# Water-Volume-Monitoring.net
KiCad netlist of a schematic drawn in EAGLE
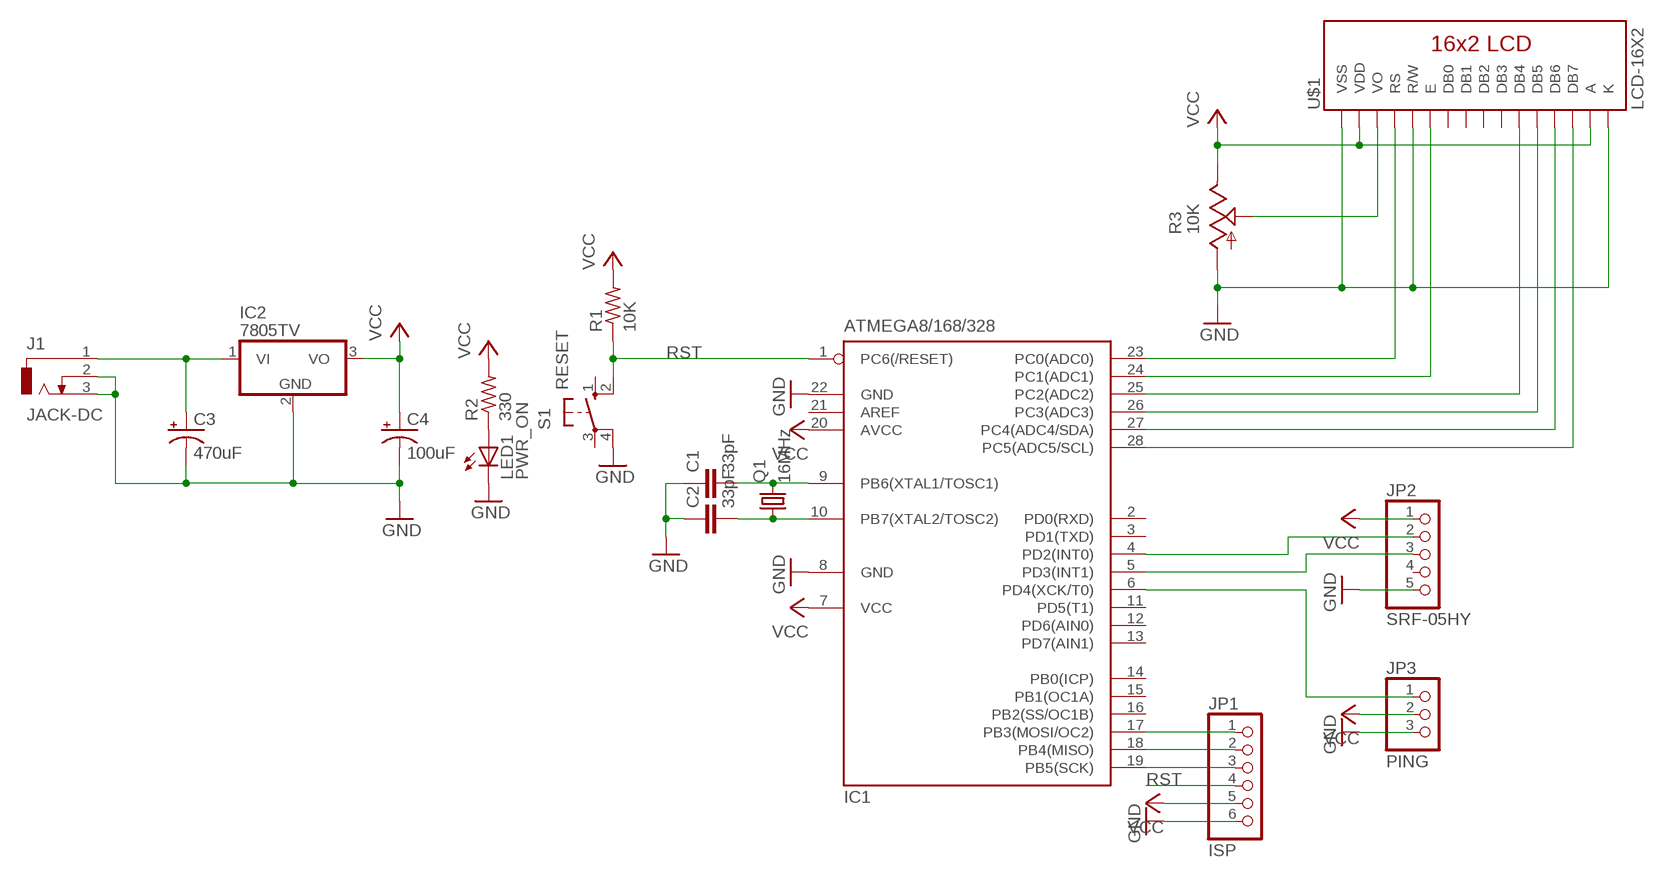
[diagram p0: schematic, sheet 1]

(export (version "E")
  (design (tool "Eeschema 10.0.6"))
  (components
    (comp (ref "C1")
      (value "33pF")
      (footprint "eagle-import:C025-024X044")
      (libsource (lib "eagle-import") (part "CAPACITOR-NONPOLAR025-024X044"))
    )
    (comp (ref "C2")
      (value "33pF")
      (footprint "eagle-import:C025-024X044")
      (libsource (lib "eagle-import") (part "CAPACITOR-NONPOLAR025-024X044"))
    )
    (comp (ref "C3")
      (value "470uF")
      (footprint "eagle-import:E2,5-6")
      (libsource (lib "eagle-import") (part "CAPACITOR-POLARE2.5-6"))
    )
    (comp (ref "C4")
      (value "100uF")
      (footprint "eagle-import:E2,5-6")
      (libsource (lib "eagle-import") (part "CAPACITOR-POLARE2.5-6"))
    )
    (comp (ref "IC1")
      (value "ATMEGA8/168/328")
      (footprint "eagle-import:DIL28-3")
      (libsource (lib "eagle-import") (part "ATMEGA8/168/328"))
    )
    (comp (ref "IC2")
      (value "7805TV")
      (footprint "eagle-import:TO220V")
      (libsource (lib "eagle-import") (part "78TV05"))
    )
    (comp (ref "J1")
      (value "JACK-DC")
      (footprint "eagle-import:DCJ0202")
      (libsource (lib "eagle-import") (part "JACK-DC"))
    )
    (comp (ref "JP1")
      (value "ISP")
      (footprint "eagle-import:1X06")
      (libsource (lib "eagle-import") (part "PINHD-1X6"))
    )
    (comp (ref "JP2")
      (value "SRF-05HY")
      (footprint "eagle-import:1X05")
      (libsource (lib "eagle-import") (part "PINHD-1X5"))
    )
    (comp (ref "JP3")
      (value "PING")
      (footprint "eagle-import:1X03")
      (libsource (lib "eagle-import") (part "PINHD-1X3"))
    )
    (comp (ref "LED1")
      (value "PWR_ON")
      (footprint "eagle-import:LED3MM")
      (libsource (lib "eagle-import") (part "LED3MM"))
    )
    (comp (ref "Q1")
      (value "16MHz")
      (footprint "eagle-import:HC49_S")
      (libsource (lib "eagle-import") (part "CRYSTALHC49S"))
    )
    (comp (ref "R1")
      (value "10K")
      (footprint "eagle-import:0207_10")
      (libsource (lib "eagle-import") (part "RESISTOR0207/10"))
    )
    (comp (ref "R2")
      (value "330")
      (footprint "eagle-import:0207_10")
      (libsource (lib "eagle-import") (part "RESISTOR0207/10"))
    )
    (comp (ref "R3")
      (value "10K")
      (footprint "eagle-import:CA6V")
      (libsource (lib "eagle-import") (part "TRIMPOTCA6V"))
    )
    (comp (ref "S1")
      (value "RESET")
      (footprint "eagle-import:B3F-10XX")
      (fields (field (name "MPN") "B3F-1000"))
      (libsource (lib "eagle-import") (part "SW-PUSHBUTTON"))
    )
    (comp (ref "U$1")
      (value "LCD-16X2")
      (footprint "eagle-import:LCD-16X2")
      (libsource (lib "eagle-import") (part "LCD-16X2"))
    )
  )
  (nets
    (net (code "1") (name "/RST") (class "Default")
      (node (ref "IC1") (pin "1") (pinfunction "PC6(/RESET)_1") (pintype "bidirectional"))
      (node (ref "JP1") (pin "4") (pinfunction "4_4") (pintype "passive"))
      (node (ref "R1") (pin "1") (pinfunction "1_1") (pintype "passive"))
      (node (ref "S1") (pin "2") (pinfunction "S1_2") (pintype "passive"))
    )
    (net (code "2") (name "GND") (class "Default")
      (node (ref "C1") (pin "1") (pinfunction "1_1") (pintype "passive"))
      (node (ref "C2") (pin "1") (pinfunction "1_1") (pintype "passive"))
      (node (ref "C3") (pin "-") (pinfunction "-_-") (pintype "passive"))
      (node (ref "C4") (pin "-") (pinfunction "-_-") (pintype "passive"))
      (node (ref "IC1") (pin "22") (pinfunction "GND_22") (pintype "power_in"))
      (node (ref "IC1") (pin "8") (pinfunction "GND_8") (pintype "power_in"))
      (node (ref "IC2") (pin "2") (pinfunction "GND_2") (pintype "passive"))
      (node (ref "J1") (pin "2") (pinfunction "2_2") (pintype "passive"))
      (node (ref "J1") (pin "3") (pinfunction "3_3") (pintype "passive"))
      (node (ref "JP1") (pin "6") (pinfunction "6_6") (pintype "passive"))
      (node (ref "JP2") (pin "5") (pinfunction "5_5") (pintype "passive"))
      (node (ref "JP3") (pin "3") (pinfunction "3_3") (pintype "passive"))
      (node (ref "LED1") (pin "K") (pinfunction "C_K") (pintype "passive"))
      (node (ref "R3") (pin "A") (pinfunction "A_A") (pintype "passive"))
      (node (ref "S1") (pin "4") (pinfunction "P1_4") (pintype "passive"))
      (node (ref "U$1") (pin "1") (pinfunction "VSS_1") (pintype "power_in"))
      (node (ref "U$1") (pin "16") (pinfunction "K_16") (pintype "power_in"))
      (node (ref "U$1") (pin "5") (pinfunction "R/W_5") (pintype "input"))
    )
    (net (code "3") (name "Net-(IC1-PB3(MOSI{slash}OC2))") (class "Default")
      (node (ref "IC1") (pin "17") (pinfunction "PB3(MOSI/OC2)_17") (pintype "bidirectional"))
      (node (ref "JP1") (pin "1") (pinfunction "1_1") (pintype "passive"))
    )
    (net (code "4") (name "Net-(IC1-PB4(MISO))") (class "Default")
      (node (ref "IC1") (pin "18") (pinfunction "PB4(MISO)_18") (pintype "bidirectional"))
      (node (ref "JP1") (pin "2") (pinfunction "2_2") (pintype "passive"))
    )
    (net (code "5") (name "Net-(IC1-PB5(SCK))") (class "Default")
      (node (ref "IC1") (pin "19") (pinfunction "PB5(SCK)_19") (pintype "bidirectional"))
      (node (ref "JP1") (pin "3") (pinfunction "3_3") (pintype "passive"))
    )
    (net (code "6") (name "Net-(IC1-PB6(XTAL1{slash}TOSC1))") (class "Default")
      (node (ref "C1") (pin "2") (pinfunction "2_2") (pintype "passive"))
      (node (ref "IC1") (pin "9") (pinfunction "PB6(XTAL1/TOSC1)_9") (pintype "bidirectional"))
      (node (ref "Q1") (pin "2") (pinfunction "2_2") (pintype "passive"))
    )
    (net (code "7") (name "Net-(IC1-PB7(XTAL2{slash}TOSC2))") (class "Default")
      (node (ref "C2") (pin "2") (pinfunction "2_2") (pintype "passive"))
      (node (ref "IC1") (pin "10") (pinfunction "PB7(XTAL2/TOSC2)_10") (pintype "bidirectional"))
      (node (ref "Q1") (pin "1") (pinfunction "1_1") (pintype "passive"))
    )
    (net (code "8") (name "Net-(IC1-PC0(ADC0))") (class "Default")
      (node (ref "IC1") (pin "23") (pinfunction "PC0(ADC0)_23") (pintype "bidirectional"))
      (node (ref "U$1") (pin "4") (pinfunction "RS_4") (pintype "input"))
    )
    (net (code "9") (name "Net-(IC1-PC1(ADC1))") (class "Default")
      (node (ref "IC1") (pin "24") (pinfunction "PC1(ADC1)_24") (pintype "bidirectional"))
      (node (ref "U$1") (pin "6") (pinfunction "E_6") (pintype "input"))
    )
    (net (code "10") (name "Net-(IC1-PC2(ADC2))") (class "Default")
      (node (ref "IC1") (pin "25") (pinfunction "PC2(ADC2)_25") (pintype "bidirectional"))
      (node (ref "U$1") (pin "11") (pinfunction "DB4_11") (pintype "bidirectional"))
    )
    (net (code "11") (name "Net-(IC1-PC3(ADC3))") (class "Default")
      (node (ref "IC1") (pin "26") (pinfunction "PC3(ADC3)_26") (pintype "bidirectional"))
      (node (ref "U$1") (pin "12") (pinfunction "DB5_12") (pintype "bidirectional"))
    )
    (net (code "12") (name "Net-(IC1-PC4(ADC4{slash}SDA))") (class "Default")
      (node (ref "IC1") (pin "27") (pinfunction "PC4(ADC4/SDA)_27") (pintype "bidirectional"))
      (node (ref "U$1") (pin "13") (pinfunction "DB6_13") (pintype "bidirectional"))
    )
    (net (code "13") (name "Net-(IC1-PC5(ADC5{slash}SCL))") (class "Default")
      (node (ref "IC1") (pin "28") (pinfunction "PC5(ADC5/SCL)_28") (pintype "bidirectional"))
      (node (ref "U$1") (pin "14") (pinfunction "DB7_14") (pintype "bidirectional"))
    )
    (net (code "14") (name "Net-(IC1-PD2(INT0))") (class "Default")
      (node (ref "IC1") (pin "4") (pinfunction "PD2(INT0)_4") (pintype "bidirectional"))
      (node (ref "JP2") (pin "2") (pinfunction "2_2") (pintype "passive"))
    )
    (net (code "15") (name "Net-(IC1-PD3(INT1))") (class "Default")
      (node (ref "IC1") (pin "5") (pinfunction "PD3(INT1)_5") (pintype "bidirectional"))
      (node (ref "JP2") (pin "3") (pinfunction "3_3") (pintype "passive"))
    )
    (net (code "16") (name "Net-(IC1-PD4(XCK{slash}T0))") (class "Default")
      (node (ref "IC1") (pin "6") (pinfunction "PD4(XCK/T0)_6") (pintype "bidirectional"))
      (node (ref "JP3") (pin "1") (pinfunction "1_1") (pintype "passive"))
    )
    (net (code "17") (name "Net-(IC2-VI)") (class "Default")
      (node (ref "C3") (pin "+") (pinfunction "+_+") (pintype "passive"))
      (node (ref "IC2") (pin "1") (pinfunction "VI_1") (pintype "input"))
      (node (ref "J1") (pin "1") (pinfunction "1_1") (pintype "passive"))
    )
    (net (code "18") (name "Net-(LED1-PadA)") (class "Default")
      (node (ref "LED1") (pin "A") (pinfunction "A_A") (pintype "passive"))
      (node (ref "R2") (pin "1") (pinfunction "1_1") (pintype "passive"))
    )
    (net (code "19") (name "Net-(U$1-VO)") (class "Default")
      (node (ref "R3") (pin "S") (pinfunction "S_S") (pintype "passive"))
      (node (ref "U$1") (pin "3") (pinfunction "VO_3") (pintype "bidirectional"))
    )
    (net (code "20") (name "VCC") (class "Default")
      (node (ref "C4") (pin "+") (pinfunction "+_+") (pintype "passive"))
      (node (ref "IC1") (pin "20") (pinfunction "AVCC_20") (pintype "power_in"))
      (node (ref "IC1") (pin "7") (pinfunction "VCC_7") (pintype "power_in"))
      (node (ref "IC2") (pin "3") (pinfunction "VO_3") (pintype "passive"))
      (node (ref "JP1") (pin "5") (pinfunction "5_5") (pintype "passive"))
      (node (ref "JP2") (pin "1") (pinfunction "1_1") (pintype "passive"))
      (node (ref "JP3") (pin "2") (pinfunction "2_2") (pintype "passive"))
      (node (ref "R1") (pin "2") (pinfunction "2_2") (pintype "passive"))
      (node (ref "R2") (pin "2") (pinfunction "2_2") (pintype "passive"))
      (node (ref "R3") (pin "E") (pinfunction "E_E") (pintype "passive"))
      (node (ref "U$1") (pin "15") (pinfunction "A_15") (pintype "power_in"))
      (node (ref "U$1") (pin "2") (pinfunction "VDD_2") (pintype "power_in"))
    )
    (net (code "21") (name "unconnected-(IC1-AREF-Pad21)") (class "Default")
      (node (ref "IC1") (pin "21") (pinfunction "AREF_21") (pintype "passive"))
    )
    (net (code "22") (name "unconnected-(IC1-PB0(ICP)-Pad14)") (class "Default")
      (node (ref "IC1") (pin "14") (pinfunction "PB0(ICP)_14") (pintype "bidirectional"))
    )
    (net (code "23") (name "unconnected-(IC1-PB1(OC1A)-Pad15)") (class "Default")
      (node (ref "IC1") (pin "15") (pinfunction "PB1(OC1A)_15") (pintype "bidirectional"))
    )
    (net (code "24") (name "unconnected-(IC1-PB2(SS{slash}OC1B)-Pad16)") (class "Default")
      (node (ref "IC1") (pin "16") (pinfunction "PB2(SS/OC1B)_16") (pintype "bidirectional"))
    )
    (net (code "25") (name "unconnected-(IC1-PD0(RXD)-Pad2)") (class "Default")
      (node (ref "IC1") (pin "2") (pinfunction "PD0(RXD)_2") (pintype "bidirectional"))
    )
    (net (code "26") (name "unconnected-(IC1-PD1(TXD)-Pad3)") (class "Default")
      (node (ref "IC1") (pin "3") (pinfunction "PD1(TXD)_3") (pintype "bidirectional"))
    )
    (net (code "27") (name "unconnected-(IC1-PD5(T1)-Pad11)") (class "Default")
      (node (ref "IC1") (pin "11") (pinfunction "PD5(T1)_11") (pintype "bidirectional"))
    )
    (net (code "28") (name "unconnected-(IC1-PD6(AIN0)-Pad12)") (class "Default")
      (node (ref "IC1") (pin "12") (pinfunction "PD6(AIN0)_12") (pintype "bidirectional"))
    )
    (net (code "29") (name "unconnected-(IC1-PD7(AIN1)-Pad13)") (class "Default")
      (node (ref "IC1") (pin "13") (pinfunction "PD7(AIN1)_13") (pintype "bidirectional"))
    )
    (net (code "30") (name "unconnected-(JP2-Pad4)") (class "Default")
      (node (ref "JP2") (pin "4") (pinfunction "4_4") (pintype "passive"))
    )
    (net (code "31") (name "unconnected-(S1-P-Pad3)") (class "Default")
      (node (ref "S1") (pin "3") (pinfunction "P_3") (pintype "passive"))
    )
    (net (code "32") (name "unconnected-(S1-S-Pad1)") (class "Default")
      (node (ref "S1") (pin "1") (pinfunction "S_1") (pintype "passive"))
    )
    (net (code "33") (name "unconnected-(U$1-DB0-Pad7)") (class "Default")
      (node (ref "U$1") (pin "7") (pinfunction "DB0_7") (pintype "bidirectional"))
    )
    (net (code "34") (name "unconnected-(U$1-DB1-Pad8)") (class "Default")
      (node (ref "U$1") (pin "8") (pinfunction "DB1_8") (pintype "bidirectional"))
    )
    (net (code "35") (name "unconnected-(U$1-DB2-Pad9)") (class "Default")
      (node (ref "U$1") (pin "9") (pinfunction "DB2_9") (pintype "bidirectional"))
    )
    (net (code "36") (name "unconnected-(U$1-DB3-Pad10)") (class "Default")
      (node (ref "U$1") (pin "10") (pinfunction "DB3_10") (pintype "bidirectional"))
    )
  )
)
